# USB2CAN_cx.net
KiCad netlist of a schematic drawn in Altium Designer
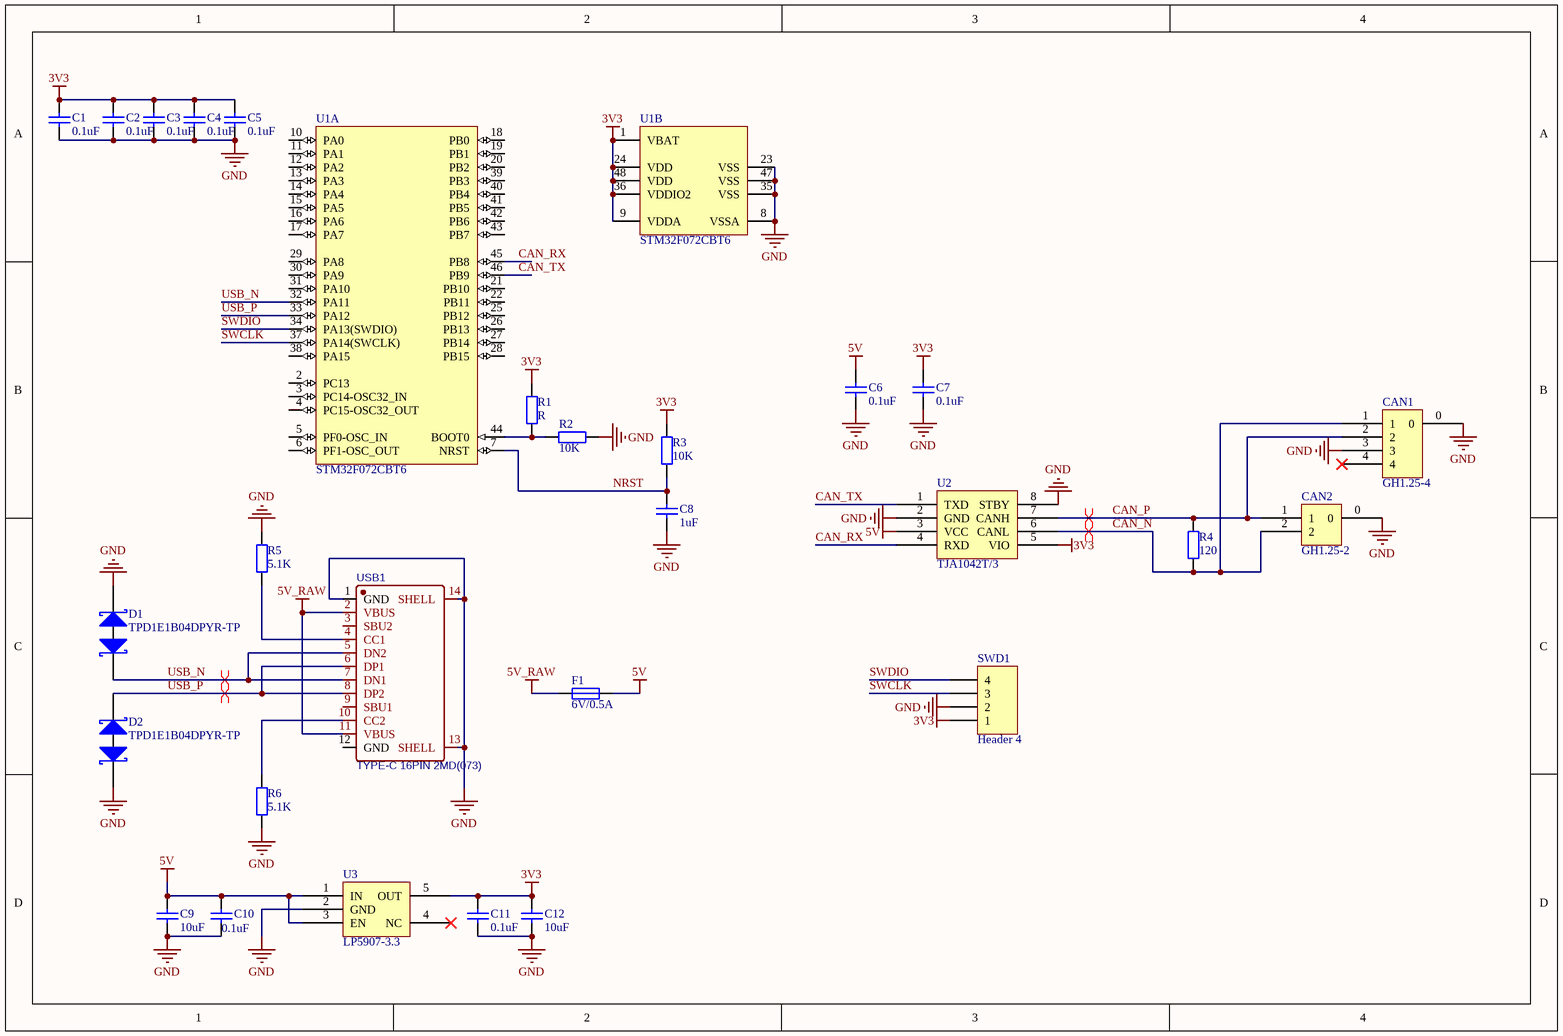
[diagram p0: USB2CAN_cx.SchDoc]

(export (version "E")
  (design (tool "Eeschema 10.0.6"))
  (components
    (comp (ref "C1")
      (value "0.1uF")
      (footprint "0603_C")
      (description "Capacitor")
      (fields (field (name "PUBLISHER") "Altium Limited"))
      (libsource (lib "常用元件") (part "CAP"))
    )
    (comp (ref "C2")
      (value "0.1uF")
      (footprint "0603_C")
      (description "Capacitor")
      (fields (field (name "PUBLISHER") "Altium Limited"))
      (libsource (lib "常用元件") (part "CAP"))
    )
    (comp (ref "C3")
      (value "0.1uF")
      (footprint "0603_C")
      (description "Capacitor")
      (fields (field (name "PUBLISHER") "Altium Limited"))
      (libsource (lib "常用元件") (part "CAP"))
    )
    (comp (ref "C4")
      (value "0.1uF")
      (footprint "0603_C")
      (description "Capacitor")
      (fields (field (name "PUBLISHER") "Altium Limited"))
      (libsource (lib "常用元件") (part "CAP"))
    )
    (comp (ref "C5")
      (value "0.1uF")
      (footprint "0603_C")
      (description "Capacitor")
      (fields (field (name "PUBLISHER") "Altium Limited"))
      (libsource (lib "常用元件") (part "CAP"))
    )
    (comp (ref "C6")
      (value "0.1uF")
      (footprint "0603_C")
      (description "Capacitor")
      (fields (field (name "PUBLISHER") "Altium Limited"))
      (libsource (lib "常用元件") (part "CAP"))
    )
    (comp (ref "C7")
      (value "0.1uF")
      (footprint "0603_C")
      (description "Capacitor")
      (fields (field (name "PUBLISHER") "Altium Limited"))
      (libsource (lib "常用元件") (part "CAP"))
    )
    (comp (ref "C8")
      (value "1uF")
      (footprint "0603_C")
      (description "Capacitor")
      (fields (field (name "PUBLISHER") "Altium Limited"))
      (libsource (lib "常用元件") (part "CAP"))
    )
    (comp (ref "C9")
      (value "10uF")
      (footprint "0603_C")
      (description "Capacitor")
      (fields (field (name "PUBLISHER") "Altium Limited"))
      (libsource (lib "常用元件") (part "CAP"))
    )
    (comp (ref "C10")
      (value "0.1uF")
      (footprint "0603_C")
      (description "Capacitor")
      (fields (field (name "PUBLISHER") "Altium Limited"))
      (libsource (lib "常用元件") (part "CAP"))
    )
    (comp (ref "C11")
      (value "0.1uF")
      (footprint "0603_C")
      (description "Capacitor")
      (fields (field (name "PUBLISHER") "Altium Limited"))
      (libsource (lib "常用元件") (part "CAP"))
    )
    (comp (ref "C12")
      (value "10uF")
      (footprint "0603_C")
      (description "Capacitor")
      (fields (field (name "PUBLISHER") "Altium Limited"))
      (libsource (lib "常用元件") (part "CAP"))
    )
    (comp (ref "CAN1")
      (value "GH1.25-4")
      (footprint "SM04B-GHS_X1251WRS-04HF-LPSW")
      (libsource (lib "第四讲集成库") (part "GH1.25-4"))
    )
    (comp (ref "CAN2")
      (value "GH1.25-2")
      (footprint "SM02B-GHS_X1251WRS-02HF-LPSW")
      (libsource (lib "第一讲集成库") (part "GH1.25-2"))
    )
    (comp (ref "D1")
      (value "TPD1E1B04DPYR-TP")
      (footprint "0402_R")
      (description "ESD Protection Diode")
      (fields (field (name "PUBLISHER") "Altium Limited"))
      (libsource (lib "CH9344") (part "ESD_Diode"))
    )
    (comp (ref "D2")
      (value "TPD1E1B04DPYR-TP")
      (footprint "0402_R")
      (description "ESD Protection Diode")
      (fields (field (name "PUBLISHER") "Altium Limited"))
      (libsource (lib "CH9344") (part "ESD_Diode"))
    )
    (comp (ref "F1")
      (value "6V/0.5A")
      (footprint "0603_R")
      (description "Fuse")
      (fields (field (name "PUBLISHER") "Altium Limited"))
      (libsource (lib "常用元件") (part "FUSE"))
    )
    (comp (ref "R1")
      (value "R")
      (footprint "0603_R")
      (description "Resistor")
      (fields (field (name "PUBLISHER") "Altium Limited"))
      (libsource (lib "常用元件") (part "RES"))
    )
    (comp (ref "R2")
      (value "10K")
      (footprint "0603_R")
      (description "Resistor")
      (fields (field (name "PUBLISHER") "Altium Limited"))
      (libsource (lib "") (part "RES_1"))
    )
    (comp (ref "R3")
      (value "10K")
      (footprint "0603_R")
      (description "Resistor")
      (fields (field (name "PUBLISHER") "Altium Limited"))
      (libsource (lib "常用元件") (part "RES"))
    )
    (comp (ref "R4")
      (value "120")
      (footprint "0603_R")
      (description "Resistor")
      (fields (field (name "PUBLISHER") "Altium Limited"))
      (libsource (lib "常用元件") (part "RES"))
    )
    (comp (ref "R5")
      (value "5.1K")
      (footprint "0603_R")
      (description "Resistor")
      (fields (field (name "PUBLISHER") "Altium Limited"))
      (libsource (lib "常用元件") (part "RES"))
    )
    (comp (ref "R6")
      (value "5.1K")
      (footprint "0603_R")
      (description "Resistor")
      (fields (field (name "PUBLISHER") "Altium Limited"))
      (libsource (lib "常用元件") (part "RES"))
    )
    (comp (ref "SWD1")
      (value "Header 4")
      (footprint "HDR1X4")
      (description "Header, 4-Pin")
      (fields (field (name "PUBLISHER") "Altium Limited"))
      (libsource (lib "Miscellaneous Connectors") (part "Header 4"))
    )
    (comp (ref "U1")
      (value "STM32F072CBT6")
      (footprint "LQFP-48_7x7x05P")
      (fields (field (name "PARTNUMBER") "STM32F050C6T6"))
      (libsource (lib "第四讲集成库") (part "STM32F072C8T6"))
    )
    (comp (ref "U2") (value "TJA1042T/3") (footprint "SOP8") (libsource (lib "第四讲集成库") (part "TJA1042T/3")))
    (comp (ref "U3") (value "LP5907-3.3") (footprint "TSOT23-5") (libsource (lib "第四讲集成库") (part "LP5907")))
    (comp (ref "USB1")
      (value "TYPE-C 16PIN 2MD(073)")
      (footprint "USB-C-SMD_TYPE-C-6PIN-2MD-073")
      (fields (field (name "BOM_SUPPLIER PART") "C2765186") (field (name "CONTRIBUTOR") "LCSC"))
      (libsource (lib "TYPEC16") (part "TYPE-C 16PIN 2MD(073)"))
    )
  )
  (nets
    (net (code "1") (name "/CAN_N") (class "Default")
      (node (ref "CAN1") (pin "1") (pinfunction "1_1") (pintype "passive"))
      (node (ref "CAN2") (pin "2") (pinfunction "2_2") (pintype "passive"))
      (node (ref "R4") (pin "1") (pinfunction "1_1") (pintype "passive"))
      (node (ref "U2") (pin "6") (pinfunction "CANL_6") (pintype "passive"))
    )
    (net (code "2") (name "/CAN_P") (class "Default")
      (node (ref "CAN1") (pin "2") (pinfunction "2_2") (pintype "passive"))
      (node (ref "CAN2") (pin "1") (pinfunction "1_1") (pintype "passive"))
      (node (ref "R4") (pin "2") (pinfunction "2_2") (pintype "passive"))
      (node (ref "U2") (pin "7") (pinfunction "CANH_7") (pintype "passive"))
    )
    (net (code "3") (name "/CAN_RX") (class "Default")
      (node (ref "U1") (pin "45") (pinfunction "PB8_45") (pintype "bidirectional"))
      (node (ref "U2") (pin "4") (pinfunction "RXD_4") (pintype "passive"))
    )
    (net (code "4") (name "/CAN_TX") (class "Default")
      (node (ref "U1") (pin "46") (pinfunction "PB9_46") (pintype "bidirectional"))
      (node (ref "U2") (pin "1") (pinfunction "TXD_1") (pintype "passive"))
    )
    (net (code "5") (name "/NRST") (class "Default")
      (node (ref "C8") (pin "2") (pinfunction "2_2") (pintype "passive"))
      (node (ref "R3") (pin "1") (pinfunction "1_1") (pintype "passive"))
      (node (ref "U1") (pin "7") (pinfunction "NRST_7") (pintype "bidirectional"))
    )
    (net (code "6") (name "/SWCLK") (class "Default")
      (node (ref "SWD1") (pin "3") (pinfunction "3_3") (pintype "passive"))
      (node (ref "U1") (pin "37") (pinfunction "PA14(SWCLK)_37") (pintype "bidirectional"))
    )
    (net (code "7") (name "/SWDIO") (class "Default")
      (node (ref "SWD1") (pin "4") (pinfunction "4_4") (pintype "passive"))
      (node (ref "U1") (pin "34") (pinfunction "PA13(SWDIO)_34") (pintype "bidirectional"))
    )
    (net (code "8") (name "/USB_N") (class "Default")
      (node (ref "D1") (pin "1") (pinfunction "A_1") (pintype "passive"))
      (node (ref "U1") (pin "32") (pinfunction "PA11_32") (pintype "bidirectional"))
      (node (ref "USB1") (pin "5") (pinfunction "DN2_5") (pintype "passive"))
      (node (ref "USB1") (pin "7") (pinfunction "DN1_7") (pintype "passive"))
    )
    (net (code "9") (name "/USB_P") (class "Default")
      (node (ref "D2") (pin "2") (pinfunction "K_2") (pintype "passive"))
      (node (ref "U1") (pin "33") (pinfunction "PA12_33") (pintype "bidirectional"))
      (node (ref "USB1") (pin "6") (pinfunction "DP1_6") (pintype "passive"))
      (node (ref "USB1") (pin "8") (pinfunction "DP2_8") (pintype "passive"))
    )
    (net (code "10") (name "3V3") (class "Default")
      (node (ref "C1") (pin "2") (pinfunction "2_2") (pintype "passive"))
      (node (ref "C11") (pin "2") (pinfunction "2_2") (pintype "passive"))
      (node (ref "C12") (pin "2") (pinfunction "2_2") (pintype "passive"))
      (node (ref "C2") (pin "2") (pinfunction "2_2") (pintype "passive"))
      (node (ref "C3") (pin "2") (pinfunction "2_2") (pintype "passive"))
      (node (ref "C4") (pin "2") (pinfunction "2_2") (pintype "passive"))
      (node (ref "C5") (pin "2") (pinfunction "2_2") (pintype "passive"))
      (node (ref "C7") (pin "1") (pinfunction "1_1") (pintype "passive"))
      (node (ref "R1") (pin "2") (pinfunction "2_2") (pintype "passive"))
      (node (ref "R3") (pin "2") (pinfunction "2_2") (pintype "passive"))
      (node (ref "SWD1") (pin "1") (pinfunction "1_1") (pintype "passive"))
      (node (ref "U1") (pin "1") (pinfunction "VBAT_1") (pintype "power_in"))
      (node (ref "U1") (pin "24") (pinfunction "VDD_24") (pintype "power_in"))
      (node (ref "U1") (pin "36") (pinfunction "VDDIO2_36") (pintype "power_in"))
      (node (ref "U1") (pin "48") (pinfunction "VDD_48") (pintype "power_in"))
      (node (ref "U1") (pin "9") (pinfunction "VDDA_9") (pintype "power_in"))
      (node (ref "U2") (pin "5") (pinfunction "VIO_5") (pintype "passive"))
      (node (ref "U3") (pin "5") (pinfunction "OUT_5") (pintype "passive"))
    )
    (net (code "11") (name "5V") (class "Default")
      (node (ref "C10") (pin "2") (pinfunction "2_2") (pintype "passive"))
      (node (ref "C6") (pin "2") (pinfunction "2_2") (pintype "passive"))
      (node (ref "C9") (pin "2") (pinfunction "2_2") (pintype "passive"))
      (node (ref "F1") (pin "2") (pinfunction "2_2") (pintype "passive"))
      (node (ref "U2") (pin "3") (pinfunction "VCC_3") (pintype "passive"))
      (node (ref "U3") (pin "1") (pinfunction "IN_1") (pintype "passive"))
      (node (ref "U3") (pin "3") (pinfunction "EN_3") (pintype "passive"))
    )
    (net (code "12") (name "5V_RAW") (class "Default")
      (node (ref "F1") (pin "1") (pinfunction "1_1") (pintype "passive"))
      (node (ref "USB1") (pin "11") (pinfunction "VBUS_11") (pintype "passive"))
      (node (ref "USB1") (pin "2") (pinfunction "VBUS_2") (pintype "passive"))
    )
    (net (code "13") (name "GND") (class "Default")
      (node (ref "C1") (pin "1") (pinfunction "1_1") (pintype "passive"))
      (node (ref "C10") (pin "1") (pinfunction "1_1") (pintype "passive"))
      (node (ref "C11") (pin "1") (pinfunction "1_1") (pintype "passive"))
      (node (ref "C12") (pin "1") (pinfunction "1_1") (pintype "passive"))
      (node (ref "C2") (pin "1") (pinfunction "1_1") (pintype "passive"))
      (node (ref "C3") (pin "1") (pinfunction "1_1") (pintype "passive"))
      (node (ref "C4") (pin "1") (pinfunction "1_1") (pintype "passive"))
      (node (ref "C5") (pin "1") (pinfunction "1_1") (pintype "passive"))
      (node (ref "C6") (pin "1") (pinfunction "1_1") (pintype "passive"))
      (node (ref "C7") (pin "2") (pinfunction "2_2") (pintype "passive"))
      (node (ref "C8") (pin "1") (pinfunction "1_1") (pintype "passive"))
      (node (ref "C9") (pin "1") (pinfunction "1_1") (pintype "passive"))
      (node (ref "CAN1") (pin "0") (pinfunction "0_0") (pintype "passive"))
      (node (ref "CAN1") (pin "3") (pinfunction "3_3") (pintype "passive"))
      (node (ref "CAN2") (pin "0") (pinfunction "0_0") (pintype "passive"))
      (node (ref "D1") (pin "2") (pinfunction "K_2") (pintype "passive"))
      (node (ref "D2") (pin "1") (pinfunction "A_1") (pintype "passive"))
      (node (ref "R2") (pin "2") (pinfunction "2_2") (pintype "passive"))
      (node (ref "R5") (pin "2") (pinfunction "2_2") (pintype "passive"))
      (node (ref "R6") (pin "1") (pinfunction "1_1") (pintype "passive"))
      (node (ref "SWD1") (pin "2") (pinfunction "2_2") (pintype "passive"))
      (node (ref "U1") (pin "23") (pinfunction "VSS_23") (pintype "power_in"))
      (node (ref "U1") (pin "35") (pinfunction "VSS_35") (pintype "power_in"))
      (node (ref "U1") (pin "47") (pinfunction "VSS_47") (pintype "power_in"))
      (node (ref "U1") (pin "8") (pinfunction "VSSA_8") (pintype "power_in"))
      (node (ref "U2") (pin "2") (pinfunction "GND_2") (pintype "passive"))
      (node (ref "U2") (pin "8") (pinfunction "STBY_8") (pintype "passive"))
      (node (ref "U3") (pin "2") (pinfunction "GND_2") (pintype "passive"))
      (node (ref "USB1") (pin "1") (pinfunction "GND_1") (pintype "passive"))
      (node (ref "USB1") (pin "13") (pinfunction "SHELL_13") (pintype "passive"))
      (node (ref "USB1") (pin "14") (pinfunction "SHELL_14") (pintype "passive"))
    )
    (net (code "14") (name "Net-(U1A-BOOT0)") (class "Default")
      (node (ref "R1") (pin "1") (pinfunction "1_1") (pintype "passive"))
      (node (ref "R2") (pin "1") (pinfunction "1_1") (pintype "passive"))
      (node (ref "U1") (pin "44") (pinfunction "BOOT0_44") (pintype "input"))
    )
    (net (code "15") (name "Net-(USB1-CC1)") (class "Default")
      (node (ref "R5") (pin "1") (pinfunction "1_1") (pintype "passive"))
      (node (ref "USB1") (pin "4") (pinfunction "CC1_4") (pintype "passive"))
    )
    (net (code "16") (name "Net-(USB1-CC2)") (class "Default")
      (node (ref "R6") (pin "2") (pinfunction "2_2") (pintype "passive"))
      (node (ref "USB1") (pin "10") (pinfunction "CC2_10") (pintype "passive"))
    )
    (net (code "17") (name "unconnected-(CAN1-Pad4)") (class "Default")
      (node (ref "CAN1") (pin "4") (pinfunction "4_4") (pintype "passive+no_connect"))
    )
    (net (code "18") (name "unconnected-(U1A-PA0-Pad10)") (class "Default")
      (node (ref "U1") (pin "10") (pinfunction "PA0_10") (pintype "bidirectional"))
    )
    (net (code "19") (name "unconnected-(U1A-PA1-Pad11)") (class "Default")
      (node (ref "U1") (pin "11") (pinfunction "PA1_11") (pintype "bidirectional"))
    )
    (net (code "20") (name "unconnected-(U1A-PA2-Pad12)") (class "Default")
      (node (ref "U1") (pin "12") (pinfunction "PA2_12") (pintype "bidirectional"))
    )
    (net (code "21") (name "unconnected-(U1A-PA3-Pad13)") (class "Default")
      (node (ref "U1") (pin "13") (pinfunction "PA3_13") (pintype "bidirectional"))
    )
    (net (code "22") (name "unconnected-(U1A-PA4-Pad14)") (class "Default")
      (node (ref "U1") (pin "14") (pinfunction "PA4_14") (pintype "bidirectional"))
    )
    (net (code "23") (name "unconnected-(U1A-PA5-Pad15)") (class "Default")
      (node (ref "U1") (pin "15") (pinfunction "PA5_15") (pintype "bidirectional"))
    )
    (net (code "24") (name "unconnected-(U1A-PA6-Pad16)") (class "Default")
      (node (ref "U1") (pin "16") (pinfunction "PA6_16") (pintype "bidirectional"))
    )
    (net (code "25") (name "unconnected-(U1A-PA7-Pad17)") (class "Default")
      (node (ref "U1") (pin "17") (pinfunction "PA7_17") (pintype "bidirectional"))
    )
    (net (code "26") (name "unconnected-(U1A-PA8-Pad29)") (class "Default")
      (node (ref "U1") (pin "29") (pinfunction "PA8_29") (pintype "bidirectional"))
    )
    (net (code "27") (name "unconnected-(U1A-PA9-Pad30)") (class "Default")
      (node (ref "U1") (pin "30") (pinfunction "PA9_30") (pintype "bidirectional"))
    )
    (net (code "28") (name "unconnected-(U1A-PA10-Pad31)") (class "Default")
      (node (ref "U1") (pin "31") (pinfunction "PA10_31") (pintype "bidirectional"))
    )
    (net (code "29") (name "unconnected-(U1A-PA15-Pad38)") (class "Default")
      (node (ref "U1") (pin "38") (pinfunction "PA15_38") (pintype "bidirectional"))
    )
    (net (code "30") (name "unconnected-(U1A-PB0-Pad18)") (class "Default")
      (node (ref "U1") (pin "18") (pinfunction "PB0_18") (pintype "bidirectional"))
    )
    (net (code "31") (name "unconnected-(U1A-PB1-Pad19)") (class "Default")
      (node (ref "U1") (pin "19") (pinfunction "PB1_19") (pintype "bidirectional"))
    )
    (net (code "32") (name "unconnected-(U1A-PB2-Pad20)") (class "Default")
      (node (ref "U1") (pin "20") (pinfunction "PB2_20") (pintype "bidirectional"))
    )
    (net (code "33") (name "unconnected-(U1A-PB3-Pad39)") (class "Default")
      (node (ref "U1") (pin "39") (pinfunction "PB3_39") (pintype "bidirectional"))
    )
    (net (code "34") (name "unconnected-(U1A-PB4-Pad40)") (class "Default")
      (node (ref "U1") (pin "40") (pinfunction "PB4_40") (pintype "bidirectional"))
    )
    (net (code "35") (name "unconnected-(U1A-PB5-Pad41)") (class "Default")
      (node (ref "U1") (pin "41") (pinfunction "PB5_41") (pintype "bidirectional"))
    )
    (net (code "36") (name "unconnected-(U1A-PB6-Pad42)") (class "Default")
      (node (ref "U1") (pin "42") (pinfunction "PB6_42") (pintype "bidirectional"))
    )
    (net (code "37") (name "unconnected-(U1A-PB7-Pad43)") (class "Default")
      (node (ref "U1") (pin "43") (pinfunction "PB7_43") (pintype "bidirectional"))
    )
    (net (code "38") (name "unconnected-(U1A-PB10-Pad21)") (class "Default")
      (node (ref "U1") (pin "21") (pinfunction "PB10_21") (pintype "bidirectional"))
    )
    (net (code "39") (name "unconnected-(U1A-PB11-Pad22)") (class "Default")
      (node (ref "U1") (pin "22") (pinfunction "PB11_22") (pintype "bidirectional"))
    )
    (net (code "40") (name "unconnected-(U1A-PB12-Pad25)") (class "Default")
      (node (ref "U1") (pin "25") (pinfunction "PB12_25") (pintype "bidirectional"))
    )
    (net (code "41") (name "unconnected-(U1A-PB13-Pad26)") (class "Default")
      (node (ref "U1") (pin "26") (pinfunction "PB13_26") (pintype "bidirectional"))
    )
    (net (code "42") (name "unconnected-(U1A-PB14-Pad27)") (class "Default")
      (node (ref "U1") (pin "27") (pinfunction "PB14_27") (pintype "bidirectional"))
    )
    (net (code "43") (name "unconnected-(U1A-PB15-Pad28)") (class "Default")
      (node (ref "U1") (pin "28") (pinfunction "PB15_28") (pintype "bidirectional"))
    )
    (net (code "44") (name "unconnected-(U1A-PC13-Pad2)") (class "Default")
      (node (ref "U1") (pin "2") (pinfunction "PC13_2") (pintype "bidirectional"))
    )
    (net (code "45") (name "unconnected-(U1A-PC14-OSC32_IN-Pad3)") (class "Default")
      (node (ref "U1") (pin "3") (pinfunction "PC14-OSC32_IN_3") (pintype "bidirectional"))
    )
    (net (code "46") (name "unconnected-(U1A-PC15-OSC32_OUT-Pad4)") (class "Default")
      (node (ref "U1") (pin "4") (pinfunction "PC15-OSC32_OUT_4") (pintype "bidirectional"))
    )
    (net (code "47") (name "unconnected-(U1A-PF0-OSC_IN-Pad5)") (class "Default")
      (node (ref "U1") (pin "5") (pinfunction "PF0-OSC_IN_5") (pintype "bidirectional"))
    )
    (net (code "48") (name "unconnected-(U1A-PF1-OSC_OUT-Pad6)") (class "Default")
      (node (ref "U1") (pin "6") (pinfunction "PF1-OSC_OUT_6") (pintype "bidirectional"))
    )
    (net (code "49") (name "unconnected-(U3-NC-Pad4)") (class "Default")
      (node (ref "U3") (pin "4") (pinfunction "NC_4") (pintype "passive+no_connect"))
    )
    (net (code "50") (name "unconnected-(USB1-GND-Pad12)") (class "Default")
      (node (ref "USB1") (pin "12") (pinfunction "GND_12") (pintype "passive"))
    )
    (net (code "51") (name "unconnected-(USB1-SBU1-Pad9)") (class "Default")
      (node (ref "USB1") (pin "9") (pinfunction "SBU1_9") (pintype "passive"))
    )
    (net (code "52") (name "unconnected-(USB1-SBU2-Pad3)") (class "Default")
      (node (ref "USB1") (pin "3") (pinfunction "SBU2_3") (pintype "passive"))
    )
  )
)
